# ppc_sys.net
KiCad netlist of a schematic drawn in Altium Designer
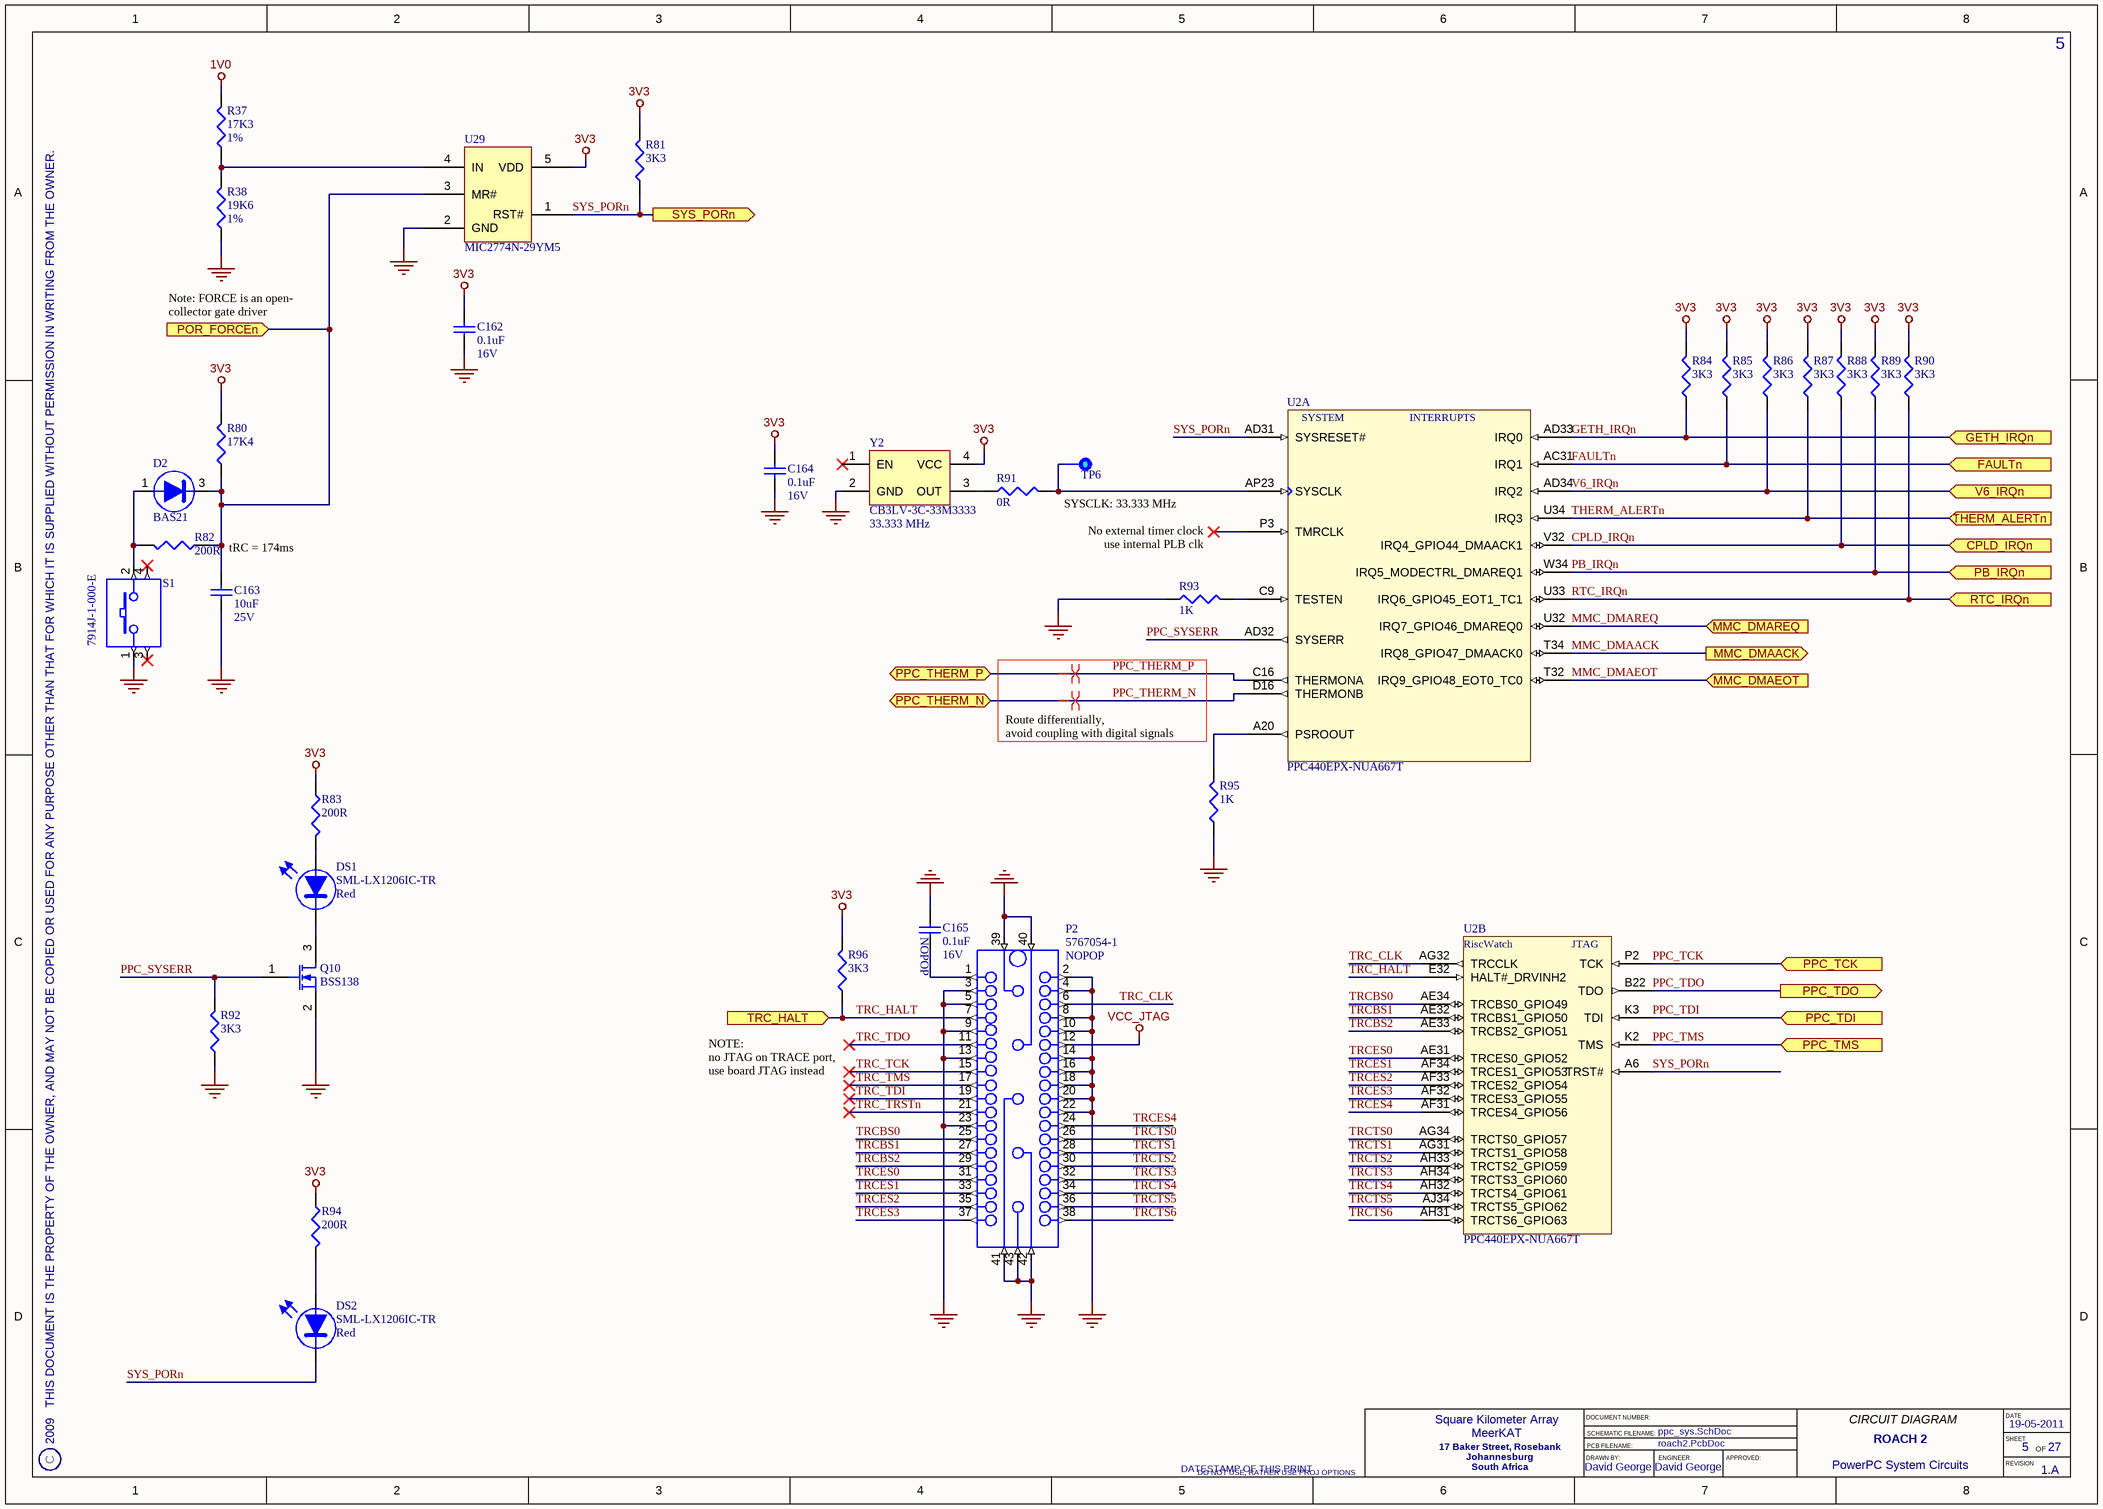
[diagram p0: ppc_sys.SchDoc]

(export (version "E")
  (design (tool "Eeschema 10.0.6"))
  (components
    (comp (ref "C162")
      (value "0.1uF")
      (footprint "CAPC1005X60L")
      (description "0.1uF, Ceramic Capacitor")
      (fields
        (field (name "RATING") "16V")
        (field (name "MANUFACTURER") "VENKEL")
        (field (name "PARTNUM") "C0402X7R160-104KN")
      )
      (libsource (lib "altium_db") (part "CapStd"))
    )
    (comp (ref "C163")
      (value "10uF")
      (footprint "CAPC3225X200L")
      (description "10uF, Ceramic Capacitor")
      (fields
        (field (name "RATING") "25V")
        (field (name "MANUFACTURER") "MURATA")
        (field (name "PARTNUM") "GRM32DR61E106KA12L")
      )
      (libsource (lib "altium_db") (part "CapStd"))
    )
    (comp (ref "C164")
      (value "0.1uF")
      (footprint "CAPC1005X60L")
      (description "0.1uF, Ceramic Capacitor")
      (fields
        (field (name "RATING") "16V")
        (field (name "MANUFACTURER") "VENKEL")
        (field (name "PARTNUM") "C0402X7R160-104KN")
      )
      (libsource (lib "altium_db") (part "CapStd"))
    )
    (comp (ref "C165")
      (value "0.1uF")
      (footprint "CAPC1005X60L")
      (description "0.1uF, Ceramic Capacitor")
      (fields
        (field (name "RATING") "16V")
        (field (name "MANUFACTURER") "VENKEL")
        (field (name "PARTNUM") "C0402X7R160-104KN")
      )
      (libsource (lib "altium_db") (part "CapStd"))
    )
    (comp (ref "D2")
      (value "BAS21")
      (footprint "SOT95P245X110-3N")
      (description "General Purpose, High Voltage, Diode")
      (fields (field (name "MANUFACTURER") "Fairchild Semi") (field (name "PARTNUM") "BAS21"))
      (libsource (lib "altium_db") (part "BAS21"))
    )
    (comp (ref "DS1")
      (value "SML-LX1206IC-TR")
      (footprint "LEDC3216X120N")
      (description "Red, Surface mount, LED, 1206")
      (fields (field (name "MANUFACTURER") "LUMEX") (field (name "COLOUR") "Red"))
      (libsource (lib "altium_db") (part "LEDSTD"))
    )
    (comp (ref "DS2")
      (value "SML-LX1206IC-TR")
      (footprint "LEDC3216X120N")
      (description "Red, Surface mount, LED, 1206")
      (fields (field (name "MANUFACTURER") "LUMEX") (field (name "COLOUR") "Red"))
      (libsource (lib "altium_db") (part "LEDSTD"))
    )
    (comp (ref "P2")
      (value "5767054-1")
      (footprint "TYCO_5767054-1")
      (description "TRACE Debug Interface Receptacle")
      (fields (field (name "PARTNUM") "5767054-1") (field (name "MANUFACTURER") "TYCO"))
      (libsource (lib "altium_db") (part "5767054"))
    )
    (comp (ref "Q10")
      (value "BSS138")
      (footprint "SOT95P245X110-3N")
      (description "N-Channel Logic Level Enhancement Mode Field Effect Transistor")
      (fields (field (name "MANUFACTURER") "Fairchild Semiconductor"))
      (libsource (lib "altium_db") (part "BSS138"))
    )
    (comp (ref "R37")
      (value "17K3")
      (footprint "RESC1005X40L")
      (description "17K3, 1.1mm x 0.5mm, Thick Film Resistor")
      (fields
        (field (name "MANUFACTURER") "ROYALOHM")
        (field (name "PARTNUM") "0402WGF1732T1E")
        (field (name "TOLERANCE") "1%")
      )
      (libsource (lib "altium_db") (part "ResStd"))
    )
    (comp (ref "R38")
      (value "19K6")
      (footprint "RESC1005X40L")
      (description "19K6, 1.1mm x 0.5mm, Thick Film Resistor")
      (fields
        (field (name "MANUFACTURER") "ROYALOHM")
        (field (name "PARTNUM") "0402WGF1962T1E")
        (field (name "TOLERANCE") "1%")
      )
      (libsource (lib "altium_db") (part "ResStd"))
    )
    (comp (ref "R80")
      (value "17K4")
      (footprint "RESC1005X40L")
      (description "17K4, 1.1mm x 0.5mm, Thick Film Resistor")
      (fields (field (name "Comment") "ResStd"))
      (libsource (lib "altium_db") (part "ResStd"))
    )
    (comp (ref "R81")
      (value "3K3")
      (footprint "RESC1005X40L")
      (description "3K3, 1.1mm x 0.5mm, Thick Film Resistor")
      (fields (field (name "MANUFACTURER") "ROYALOHM") (field (name "PARTNUM") "0402WGJ0332T1E"))
      (libsource (lib "altium_db") (part "ResStd"))
    )
    (comp (ref "R82")
      (value "200R")
      (footprint "RESC1005X40L")
      (description "200R, 1.1mm x 0.5mm, Thick Film Resistor")
      (fields (field (name "MANUFACTURER") "ROYALOHM") (field (name "PARTNUM") "0402WGF0201T1E"))
      (libsource (lib "altium_db") (part "ResStd"))
    )
    (comp (ref "R83")
      (value "200R")
      (footprint "RESC1005X40L")
      (description "200R, 1.1mm x 0.5mm, Thick Film Resistor")
      (fields (field (name "MANUFACTURER") "ROYALOHM") (field (name "PARTNUM") "0402WGF0201T1E"))
      (libsource (lib "altium_db") (part "ResStd"))
    )
    (comp (ref "R84")
      (value "3K3")
      (footprint "RESC1005X40L")
      (description "3K3, 1.1mm x 0.5mm, Thick Film Resistor")
      (fields (field (name "MANUFACTURER") "ROYALOHM") (field (name "PARTNUM") "0402WGJ0332T1E"))
      (libsource (lib "altium_db") (part "ResStd"))
    )
    (comp (ref "R85")
      (value "3K3")
      (footprint "RESC1005X40L")
      (description "3K3, 1.1mm x 0.5mm, Thick Film Resistor")
      (fields (field (name "MANUFACTURER") "ROYALOHM") (field (name "PARTNUM") "0402WGJ0332T1E"))
      (libsource (lib "altium_db") (part "ResStd"))
    )
    (comp (ref "R86")
      (value "3K3")
      (footprint "RESC1005X40L")
      (description "3K3, 1.1mm x 0.5mm, Thick Film Resistor")
      (fields (field (name "MANUFACTURER") "ROYALOHM") (field (name "PARTNUM") "0402WGJ0332T1E"))
      (libsource (lib "altium_db") (part "ResStd"))
    )
    (comp (ref "R87")
      (value "3K3")
      (footprint "RESC1005X40L")
      (description "3K3, 1.1mm x 0.5mm, Thick Film Resistor")
      (fields (field (name "MANUFACTURER") "ROYALOHM") (field (name "PARTNUM") "0402WGJ0332T1E"))
      (libsource (lib "altium_db") (part "ResStd"))
    )
    (comp (ref "R88")
      (value "3K3")
      (footprint "RESC1005X40L")
      (description "3K3, 1.1mm x 0.5mm, Thick Film Resistor")
      (fields (field (name "MANUFACTURER") "ROYALOHM") (field (name "PARTNUM") "0402WGJ0332T1E"))
      (libsource (lib "altium_db") (part "ResStd"))
    )
    (comp (ref "R89")
      (value "3K3")
      (footprint "RESC1005X40L")
      (description "3K3, 1.1mm x 0.5mm, Thick Film Resistor")
      (fields (field (name "MANUFACTURER") "ROYALOHM") (field (name "PARTNUM") "0402WGJ0332T1E"))
      (libsource (lib "altium_db") (part "ResStd"))
    )
    (comp (ref "R90")
      (value "3K3")
      (footprint "RESC1005X40L")
      (description "3K3, 1.1mm x 0.5mm, Thick Film Resistor")
      (fields (field (name "MANUFACTURER") "ROYALOHM") (field (name "PARTNUM") "0402WGJ0332T1E"))
      (libsource (lib "altium_db") (part "ResStd"))
    )
    (comp (ref "R91")
      (value "0R")
      (footprint "RESC1005X40L")
      (description "0R, 1.1mm x 0.5mm, Thick Film Resistor")
      (fields (field (name "MANUFACTURER") "ROYALOHM") (field (name "PARTNUM") "0402WG00000T1E"))
      (libsource (lib "altium_db") (part "ResStd"))
    )
    (comp (ref "R92")
      (value "3K3")
      (footprint "RESC1005X40L")
      (description "3K3, 1.1mm x 0.5mm, Thick Film Resistor")
      (fields (field (name "MANUFACTURER") "ROYALOHM") (field (name "PARTNUM") "0402WGJ0332T1E"))
      (libsource (lib "altium_db") (part "ResStd"))
    )
    (comp (ref "R93")
      (value "1K")
      (footprint "RESC1005X40L")
      (description "1K, 1.1mm x 0.5mm, Thick Film Resistor")
      (fields (field (name "MANUFACTURER") "ROYALOHM") (field (name "PARTNUM") "0402WGJ0102T1E"))
      (libsource (lib "altium_db") (part "ResStd"))
    )
    (comp (ref "R94")
      (value "200R")
      (footprint "RESC1005X40L")
      (description "200R, 1.1mm x 0.5mm, Thick Film Resistor")
      (fields (field (name "MANUFACTURER") "ROYALOHM") (field (name "PARTNUM") "0402WGF0201T1E"))
      (libsource (lib "altium_db") (part "ResStd"))
    )
    (comp (ref "R95")
      (value "1K")
      (footprint "RESC1005X40L")
      (description "1K, 1.1mm x 0.5mm, Thick Film Resistor")
      (fields (field (name "MANUFACTURER") "ROYALOHM") (field (name "PARTNUM") "0402WGJ0102T1E"))
      (libsource (lib "altium_db") (part "ResStd"))
    )
    (comp (ref "R96")
      (value "3K3")
      (footprint "RESC1005X40L")
      (description "3K3, 1.1mm x 0.5mm, Thick Film Resistor")
      (fields (field (name "MANUFACTURER") "ROYALOHM") (field (name "PARTNUM") "0402WGJ0332T1E"))
      (libsource (lib "altium_db") (part "ResStd"))
    )
    (comp (ref "S1")
      (value "7914J-1-000-E")
      (footprint "7914J-X-XXX-X")
      (description "4mm, Surface mount, Sealed Key Switch")
      (fields (field (name "PARTNUM") "7914J-1-000-E") (field (name "MANUFACTURER") "BOURNS"))
      (libsource (lib "altium_db") (part "7914X-X-XXX-X"))
    )
    (comp (ref "TP6")
      (value "Testpoint")
      (footprint "TP100")
      (description "1mm Diameter, through-hole, Circular Test-point")
      (libsource (lib "altium_db") (part "Testpoint"))
    )
    (comp (ref "U2")
      (value "PPC440EPX-NUA667T")
      (footprint "TE-PBGA680")
      (description "667MHz, non-RoHS, PPC440EPx uProcessor")
      (fields (field (name "MANUFACTURER") "Applied Micro"))
      (libsource (lib "altium_db") (part "PPC440EPX"))
    )
    (comp (ref "U29")
      (value "MIC2774N-29YM5")
      (footprint "SOT23-5")
      (description "Dual-power low voltage supervisor")
      (fields (field (name "MANUFACTURER") "Micrel"))
      (libsource (lib "altium_db") (part "MIC2774N-29"))
    )
    (comp (ref "Y2")
      (value "CB3LV-3C-33M3333")
      (footprint "CB3X-X-XMX")
      (description "Surface mount, 33.3333 MHz, 3V3 Clock, oscillator")
      (fields
        (field (name "PARTNUM") "CB3LV-3C-33M3333")
        (field (name "FREQUENCY") "33.333 MHz")
        (field (name "MANUFACTURER") "CTS")
      )
      (libsource (lib "altium_db") (part "CB3LV-3C-33M3333"))
    )
  )
  (nets
    (net (code "1") (name "/CPLD_IRQn") (class "Default")
      (node (ref "R88") (pin "1") (pinfunction "1_1") (pintype "passive"))
      (node (ref "U2") (pin "V32") (pinfunction "IRQ4_GPIO44_DMAACK1_V32") (pintype "bidirectional"))
    )
    (net (code "2") (name "/FAULTn") (class "Default")
      (node (ref "R85") (pin "1") (pinfunction "1_1") (pintype "passive"))
      (node (ref "U2") (pin "AC31") (pinfunction "IRQ1_AC31") (pintype "input"))
    )
    (net (code "3") (name "/GETH_IRQn") (class "Default")
      (node (ref "R84") (pin "1") (pinfunction "1_1") (pintype "passive"))
      (node (ref "U2") (pin "AD33") (pinfunction "IRQ0_AD33") (pintype "input"))
    )
    (net (code "4") (name "/MMC_DMAACK") (class "Default")
      (node (ref "U2") (pin "T34") (pinfunction "IRQ8_GPIO47_DMAACK0_T34") (pintype "bidirectional"))
    )
    (net (code "5") (name "/MMC_DMAEOT") (class "Default")
      (node (ref "U2") (pin "T32") (pinfunction "IRQ9_GPIO48_EOT0_TC0_T32") (pintype "bidirectional"))
    )
    (net (code "6") (name "/MMC_DMAREQ") (class "Default")
      (node (ref "U2") (pin "U32") (pinfunction "IRQ7_GPIO46_DMAREQ0_U32") (pintype "bidirectional"))
    )
    (net (code "7") (name "/PB_IRQn") (class "Default")
      (node (ref "R89") (pin "1") (pinfunction "1_1") (pintype "passive"))
      (node (ref "U2") (pin "W34") (pinfunction "IRQ5_MODECTRL_DMAREQ1_W34") (pintype "bidirectional"))
    )
    (net (code "8") (name "/POR_FORCEn") (class "Default")
      (node (ref "C163") (pin "2") (pinfunction "2_2") (pintype "passive"))
      (node (ref "D2") (pin "3") (pinfunction "K_3") (pintype "passive"))
      (node (ref "R80") (pin "1") (pinfunction "1_1") (pintype "passive"))
      (node (ref "R82") (pin "1") (pinfunction "1_1") (pintype "passive"))
      (node (ref "U29") (pin "3") (pinfunction "MR#_3") (pintype "passive"))
    )
    (net (code "9") (name "/PPC_SYSERR") (class "Default")
      (node (ref "Q10") (pin "1") (pinfunction "G_1") (pintype "passive"))
      (node (ref "R92") (pin "2") (pinfunction "2_2") (pintype "passive"))
      (node (ref "U2") (pin "AD32") (pinfunction "SYSERR_AD32") (pintype "output"))
    )
    (net (code "10") (name "/PPC_TCK") (class "Default")
      (node (ref "U2") (pin "P2") (pinfunction "TCK_P2") (pintype "input"))
    )
    (net (code "11") (name "/PPC_TDI") (class "Default")
      (node (ref "U2") (pin "K3") (pinfunction "TDI_K3") (pintype "input"))
    )
    (net (code "12") (name "/PPC_TDO") (class "Default")
      (node (ref "U2") (pin "B22") (pinfunction "TDO_B22") (pintype "output"))
    )
    (net (code "13") (name "/PPC_THERM_N") (class "Default")
      (node (ref "U2") (pin "D16") (pinfunction "THERMONB_D16") (pintype "output"))
    )
    (net (code "14") (name "/PPC_THERM_P") (class "Default")
      (node (ref "U2") (pin "C16") (pinfunction "THERMONA_C16") (pintype "output"))
    )
    (net (code "15") (name "/PPC_TMS") (class "Default")
      (node (ref "U2") (pin "K2") (pinfunction "TMS_K2") (pintype "input"))
    )
    (net (code "16") (name "/RTC_IRQn") (class "Default")
      (node (ref "R90") (pin "1") (pinfunction "1_1") (pintype "passive"))
      (node (ref "U2") (pin "U33") (pinfunction "IRQ6_GPIO45_EOT1_TC1_U33") (pintype "bidirectional"))
    )
    (net (code "17") (name "/SYS_PORn") (class "Default")
      (node (ref "DS2") (pin "1") (pinfunction "K_1") (pintype "passive"))
      (node (ref "R81") (pin "1") (pinfunction "1_1") (pintype "passive"))
      (node (ref "U2") (pin "A6") (pinfunction "TRST#_A6") (pintype "input"))
      (node (ref "U2") (pin "AD31") (pinfunction "SYSRESET#_AD31") (pintype "input"))
      (node (ref "U29") (pin "1") (pinfunction "RST#_1") (pintype "passive"))
    )
    (net (code "18") (name "/THERM_ALERTn") (class "Default")
      (node (ref "R87") (pin "1") (pinfunction "1_1") (pintype "passive"))
      (node (ref "U2") (pin "U34") (pinfunction "IRQ3_U34") (pintype "input"))
    )
    (net (code "19") (name "/TRCBS0") (class "Default")
      (node (ref "P2") (pin "25") (pinfunction "25_25") (pintype "output"))
      (node (ref "U2") (pin "AE34") (pinfunction "TRCBS0_GPIO49_AE34") (pintype "bidirectional"))
    )
    (net (code "20") (name "/TRCBS1") (class "Default")
      (node (ref "P2") (pin "27") (pinfunction "27_27") (pintype "output"))
      (node (ref "U2") (pin "AE32") (pinfunction "TRCBS1_GPIO50_AE32") (pintype "bidirectional"))
    )
    (net (code "21") (name "/TRCBS2") (class "Default")
      (node (ref "P2") (pin "29") (pinfunction "29_29") (pintype "output"))
      (node (ref "U2") (pin "AE33") (pinfunction "TRCBS2_GPIO51_AE33") (pintype "bidirectional"))
    )
    (net (code "22") (name "/TRCES0") (class "Default")
      (node (ref "P2") (pin "31") (pinfunction "31_31") (pintype "output"))
      (node (ref "U2") (pin "AE31") (pinfunction "TRCES0_GPIO52_AE31") (pintype "bidirectional"))
    )
    (net (code "23") (name "/TRCES1") (class "Default")
      (node (ref "P2") (pin "33") (pinfunction "33_33") (pintype "output"))
      (node (ref "U2") (pin "AF34") (pinfunction "TRCES1_GPIO53_AF34") (pintype "bidirectional"))
    )
    (net (code "24") (name "/TRCES2") (class "Default")
      (node (ref "P2") (pin "35") (pinfunction "35_35") (pintype "output"))
      (node (ref "U2") (pin "AF33") (pinfunction "TRCES2_GPIO54_AF33") (pintype "bidirectional"))
    )
    (net (code "25") (name "/TRCES3") (class "Default")
      (node (ref "P2") (pin "37") (pinfunction "37_37") (pintype "output"))
      (node (ref "U2") (pin "AF32") (pinfunction "TRCES3_GPIO55_AF32") (pintype "bidirectional"))
    )
    (net (code "26") (name "/TRCES4") (class "Default")
      (node (ref "P2") (pin "24") (pinfunction "24_24") (pintype "output"))
      (node (ref "U2") (pin "AF31") (pinfunction "TRCES4_GPIO56_AF31") (pintype "bidirectional"))
    )
    (net (code "27") (name "/TRCTS0") (class "Default")
      (node (ref "P2") (pin "26") (pinfunction "26_26") (pintype "output"))
      (node (ref "U2") (pin "AG34") (pinfunction "TRCTS0_GPIO57_AG34") (pintype "bidirectional"))
    )
    (net (code "28") (name "/TRCTS1") (class "Default")
      (node (ref "P2") (pin "28") (pinfunction "28_28") (pintype "output"))
      (node (ref "U2") (pin "AG31") (pinfunction "TRCTS1_GPIO58_AG31") (pintype "bidirectional"))
    )
    (net (code "29") (name "/TRCTS2") (class "Default")
      (node (ref "P2") (pin "30") (pinfunction "30_30") (pintype "output"))
      (node (ref "U2") (pin "AH33") (pinfunction "TRCTS2_GPIO59_AH33") (pintype "bidirectional"))
    )
    (net (code "30") (name "/TRCTS3") (class "Default")
      (node (ref "P2") (pin "32") (pinfunction "32_32") (pintype "output"))
      (node (ref "U2") (pin "AH34") (pinfunction "TRCTS3_GPIO60_AH34") (pintype "bidirectional"))
    )
    (net (code "31") (name "/TRCTS4") (class "Default")
      (node (ref "P2") (pin "34") (pinfunction "34_34") (pintype "output"))
      (node (ref "U2") (pin "AH32") (pinfunction "TRCTS4_GPIO61_AH32") (pintype "bidirectional"))
    )
    (net (code "32") (name "/TRCTS5") (class "Default")
      (node (ref "P2") (pin "36") (pinfunction "36_36") (pintype "output"))
      (node (ref "U2") (pin "AJ34") (pinfunction "TRCTS5_GPIO62_AJ34") (pintype "bidirectional"))
    )
    (net (code "33") (name "/TRCTS6") (class "Default")
      (node (ref "P2") (pin "38") (pinfunction "38_38") (pintype "output"))
      (node (ref "U2") (pin "AH31") (pinfunction "TRCTS6_GPIO63_AH31") (pintype "bidirectional"))
    )
    (net (code "34") (name "/TRC_CLK") (class "Default")
      (node (ref "P2") (pin "6") (pinfunction "6_6") (pintype "output"))
      (node (ref "U2") (pin "AG32") (pinfunction "TRCCLK_AG32") (pintype "output"))
    )
    (net (code "35") (name "/TRC_HALT") (class "Default")
      (node (ref "P2") (pin "7") (pinfunction "7_7") (pintype "output"))
      (node (ref "R96") (pin "1") (pinfunction "1_1") (pintype "passive"))
      (node (ref "U2") (pin "E32") (pinfunction "HALT#_DRVINH2_E32") (pintype "input"))
    )
    (net (code "36") (name "/TRC_TCK") (class "Default")
      (node (ref "P2") (pin "15") (pinfunction "15_15") (pintype "output+no_connect"))
    )
    (net (code "37") (name "/TRC_TDI") (class "Default")
      (node (ref "P2") (pin "19") (pinfunction "19_19") (pintype "output+no_connect"))
    )
    (net (code "38") (name "/TRC_TDO") (class "Default")
      (node (ref "P2") (pin "11") (pinfunction "11_11") (pintype "output+no_connect"))
    )
    (net (code "39") (name "/TRC_TMS") (class "Default")
      (node (ref "P2") (pin "17") (pinfunction "17_17") (pintype "output+no_connect"))
    )
    (net (code "40") (name "/TRC_TRSTn") (class "Default")
      (node (ref "P2") (pin "21") (pinfunction "21_21") (pintype "output+no_connect"))
    )
    (net (code "41") (name "/V6_IRQn") (class "Default")
      (node (ref "R86") (pin "1") (pinfunction "1_1") (pintype "passive"))
      (node (ref "U2") (pin "AD34") (pinfunction "IRQ2_AD34") (pintype "input"))
    )
    (net (code "42") (name "1V0") (class "Default")
      (node (ref "R37") (pin "2") (pinfunction "2_2") (pintype "passive"))
    )
    (net (code "43") (name "3V3") (class "Default")
      (node (ref "C162") (pin "2") (pinfunction "2_2") (pintype "passive"))
      (node (ref "C164") (pin "2") (pinfunction "2_2") (pintype "passive"))
      (node (ref "R80") (pin "2") (pinfunction "2_2") (pintype "passive"))
      (node (ref "R81") (pin "2") (pinfunction "2_2") (pintype "passive"))
      (node (ref "R83") (pin "1") (pinfunction "1_1") (pintype "passive"))
      (node (ref "R84") (pin "2") (pinfunction "2_2") (pintype "passive"))
      (node (ref "R85") (pin "2") (pinfunction "2_2") (pintype "passive"))
      (node (ref "R86") (pin "2") (pinfunction "2_2") (pintype "passive"))
      (node (ref "R87") (pin "2") (pinfunction "2_2") (pintype "passive"))
      (node (ref "R88") (pin "2") (pinfunction "2_2") (pintype "passive"))
      (node (ref "R89") (pin "2") (pinfunction "2_2") (pintype "passive"))
      (node (ref "R90") (pin "2") (pinfunction "2_2") (pintype "passive"))
      (node (ref "R94") (pin "1") (pinfunction "1_1") (pintype "passive"))
      (node (ref "R96") (pin "2") (pinfunction "2_2") (pintype "passive"))
      (node (ref "U29") (pin "5") (pinfunction "VDD_5") (pintype "passive"))
      (node (ref "Y2") (pin "4") (pinfunction "VCC_4") (pintype "passive"))
    )
    (net (code "44") (name "GND") (class "Default")
      (node (ref "C162") (pin "1") (pinfunction "1_1") (pintype "passive"))
      (node (ref "C163") (pin "1") (pinfunction "1_1") (pintype "passive"))
      (node (ref "C164") (pin "1") (pinfunction "1_1") (pintype "passive"))
      (node (ref "C165") (pin "2") (pinfunction "2_2") (pintype "passive"))
      (node (ref "P2") (pin "10") (pinfunction "10_10") (pintype "output"))
      (node (ref "P2") (pin "13") (pinfunction "13_13") (pintype "output"))
      (node (ref "P2") (pin "14") (pinfunction "14_14") (pintype "output"))
      (node (ref "P2") (pin "16") (pinfunction "16_16") (pintype "output"))
      (node (ref "P2") (pin "18") (pinfunction "18_18") (pintype "output"))
      (node (ref "P2") (pin "2") (pinfunction "2_2") (pintype "output"))
      (node (ref "P2") (pin "20") (pinfunction "20_20") (pintype "output"))
      (node (ref "P2") (pin "22") (pinfunction "22_22") (pintype "output"))
      (node (ref "P2") (pin "23") (pinfunction "23_23") (pintype "output"))
      (node (ref "P2") (pin "3") (pinfunction "3_3") (pintype "output"))
      (node (ref "P2") (pin "39") (pinfunction "39_39") (pintype "input"))
      (node (ref "P2") (pin "4") (pinfunction "4_4") (pintype "output"))
      (node (ref "P2") (pin "40") (pinfunction "40_40") (pintype "input"))
      (node (ref "P2") (pin "41") (pinfunction "41_41") (pintype "input"))
      (node (ref "P2") (pin "42") (pinfunction "42_42") (pintype "input"))
      (node (ref "P2") (pin "43") (pinfunction "43_43") (pintype "input"))
      (node (ref "P2") (pin "5") (pinfunction "5_5") (pintype "output"))
      (node (ref "P2") (pin "8") (pinfunction "8_8") (pintype "output"))
      (node (ref "P2") (pin "9") (pinfunction "9_9") (pintype "output"))
      (node (ref "Q10") (pin "2") (pinfunction "S_2") (pintype "passive"))
      (node (ref "R38") (pin "1") (pinfunction "1_1") (pintype "passive"))
      (node (ref "R92") (pin "1") (pinfunction "1_1") (pintype "passive"))
      (node (ref "R93") (pin "1") (pinfunction "1_1") (pintype "passive"))
      (node (ref "R95") (pin "1") (pinfunction "1_1") (pintype "passive"))
      (node (ref "S1") (pin "1") (pinfunction "1_1") (pintype "output"))
      (node (ref "U29") (pin "2") (pinfunction "GND_2") (pintype "passive"))
      (node (ref "Y2") (pin "2") (pinfunction "GND_2") (pintype "passive"))
    )
    (net (code "45") (name "Net-(C165-Pad1)") (class "Default")
      (node (ref "C165") (pin "1") (pinfunction "1_1") (pintype "passive"))
      (node (ref "P2") (pin "1") (pinfunction "1_1") (pintype "output"))
    )
    (net (code "46") (name "Net-(D2-A)") (class "Default")
      (node (ref "D2") (pin "1") (pinfunction "A_1") (pintype "passive"))
      (node (ref "R82") (pin "2") (pinfunction "2_2") (pintype "passive"))
      (node (ref "S1") (pin "2") (pinfunction "2_2") (pintype "output"))
    )
    (net (code "47") (name "Net-(DS1-A)") (class "Default")
      (node (ref "DS1") (pin "2") (pinfunction "A_2") (pintype "passive"))
      (node (ref "R83") (pin "2") (pinfunction "2_2") (pintype "passive"))
    )
    (net (code "48") (name "Net-(DS1-K)") (class "Default")
      (node (ref "DS1") (pin "1") (pinfunction "K_1") (pintype "passive"))
      (node (ref "Q10") (pin "3") (pinfunction "D_3") (pintype "passive"))
    )
    (net (code "49") (name "Net-(DS2-A)") (class "Default")
      (node (ref "DS2") (pin "2") (pinfunction "A_2") (pintype "passive"))
      (node (ref "R94") (pin "2") (pinfunction "2_2") (pintype "passive"))
    )
    (net (code "50") (name "Net-(U2A-PSROOUT)") (class "Default")
      (node (ref "R95") (pin "2") (pinfunction "2_2") (pintype "passive"))
      (node (ref "U2") (pin "A20") (pinfunction "PSROOUT_A20") (pintype "output"))
    )
    (net (code "51") (name "Net-(U2A-SYSCLK)") (class "Default")
      (node (ref "R91") (pin "2") (pinfunction "2_2") (pintype "passive"))
      (node (ref "TP6") (pin "1") (pinfunction "1_1") (pintype "passive"))
      (node (ref "U2") (pin "AP23") (pinfunction "SYSCLK_AP23") (pintype "input"))
    )
    (net (code "52") (name "Net-(U2A-TESTEN)") (class "Default")
      (node (ref "R93") (pin "2") (pinfunction "2_2") (pintype "passive"))
      (node (ref "U2") (pin "C9") (pinfunction "TESTEN_C9") (pintype "input"))
    )
    (net (code "53") (name "Net-(U29-IN)") (class "Default")
      (node (ref "R37") (pin "1") (pinfunction "1_1") (pintype "passive"))
      (node (ref "R38") (pin "2") (pinfunction "2_2") (pintype "passive"))
      (node (ref "U29") (pin "4") (pinfunction "IN_4") (pintype "passive"))
    )
    (net (code "54") (name "Net-(Y2-OUT)") (class "Default")
      (node (ref "R91") (pin "1") (pinfunction "1_1") (pintype "passive"))
      (node (ref "Y2") (pin "3") (pinfunction "OUT_3") (pintype "passive"))
    )
    (net (code "55") (name "VCC_JTAG") (class "Default")
      (node (ref "P2") (pin "12") (pinfunction "12_12") (pintype "output"))
    )
    (net (code "56") (name "unconnected-(D2-NC-Pad2)") (class "Default")
      (node (ref "D2") (pin "2") (pinfunction "NC_2") (pintype "passive"))
    )
    (net (code "57") (name "unconnected-(S1-Pad3)") (class "Default")
      (node (ref "S1") (pin "3") (pinfunction "3_3") (pintype "output+no_connect"))
    )
    (net (code "58") (name "unconnected-(S1-Pad4)") (class "Default")
      (node (ref "S1") (pin "4") (pinfunction "4_4") (pintype "output+no_connect"))
    )
    (net (code "59") (name "unconnected-(U2A-TMRCLK-PadP3)") (class "Default")
      (node (ref "U2") (pin "P3") (pinfunction "TMRCLK_P3") (pintype "input+no_connect"))
    )
    (net (code "60") (name "unconnected-(Y2-EN-Pad1)") (class "Default")
      (node (ref "Y2") (pin "1") (pinfunction "EN_1") (pintype "passive+no_connect"))
    )
  )
)
